# ATTiny85_5LED_R1.net
KiCad netlist of a schematic drawn in EAGLE
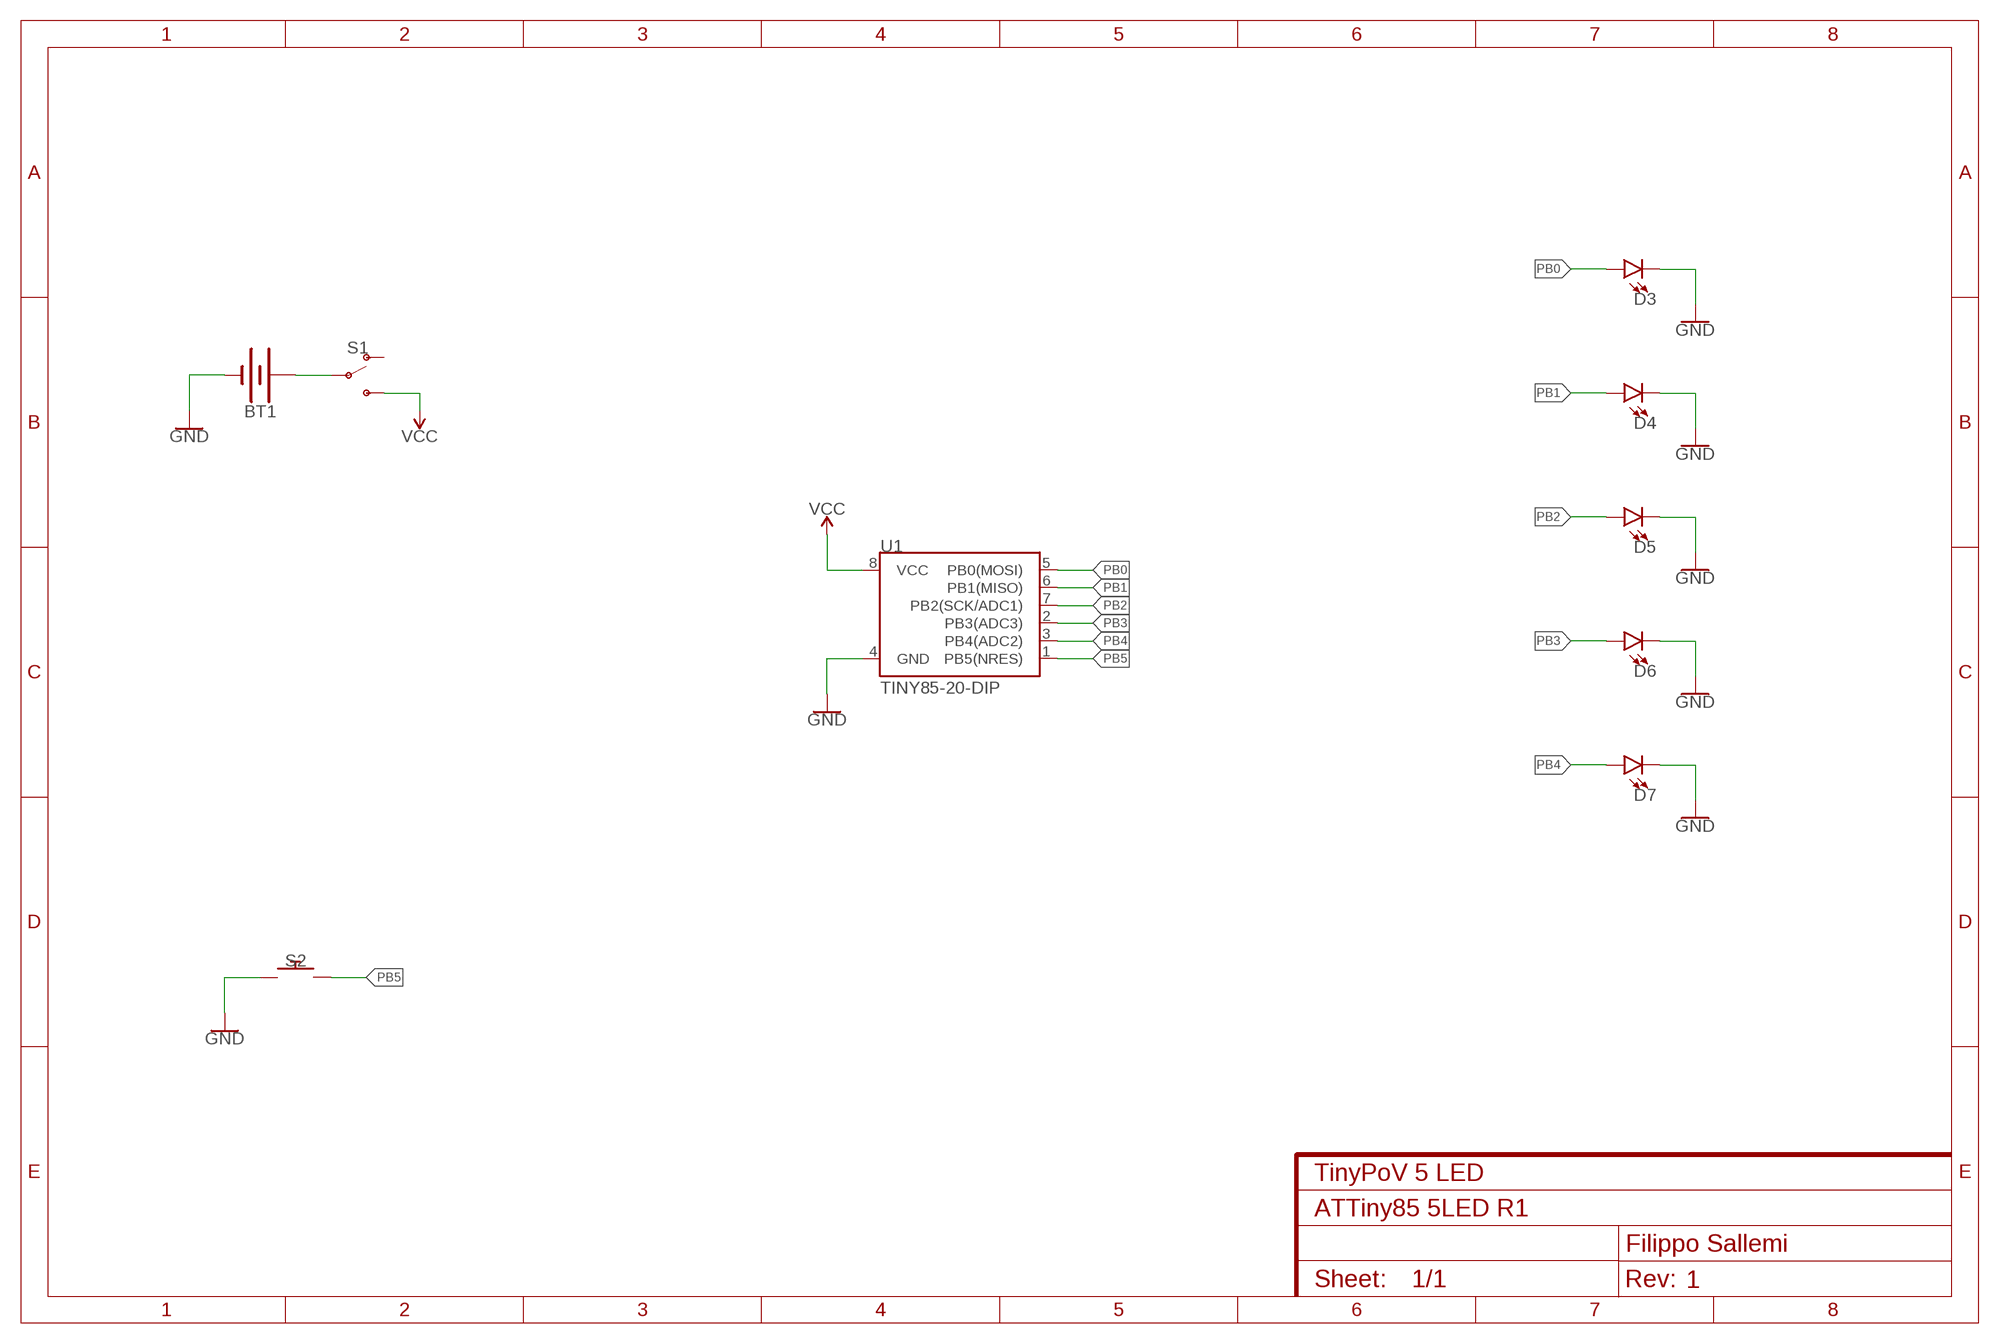
[diagram p0: schematic, sheet 1]

(export (version "E")
  (design (tool "Eeschema 10.0.6"))
  (components
    (comp (ref "BT1")
      (value "BATTERY-20MM_PTH")
      (footprint "eagle-import:BATTCOM_20MM_PTH")
      (libsource (lib "eagle-import") (part "BATTERY-20MM_PTH"))
    )
    (comp (ref "D3")
      (value "LED5MM")
      (footprint "eagle-import:LED_5MM")
      (libsource (lib "eagle-import") (part "LED5MM"))
    )
    (comp (ref "D4")
      (value "LED5MM")
      (footprint "eagle-import:LED_5MM")
      (libsource (lib "eagle-import") (part "LED5MM"))
    )
    (comp (ref "D5")
      (value "LED5MM")
      (footprint "eagle-import:LED_5MM")
      (libsource (lib "eagle-import") (part "LED5MM"))
    )
    (comp (ref "D6")
      (value "LED5MM")
      (footprint "eagle-import:LED_5MM")
      (libsource (lib "eagle-import") (part "LED5MM"))
    )
    (comp (ref "D7")
      (value "LED5MM")
      (footprint "eagle-import:LED_5MM")
      (libsource (lib "eagle-import") (part "LED5MM"))
    )
    (comp (ref "S1")
      (value "SWITCH-SPDT-PTH-11.6X4.0MM-KIT")
      (footprint "eagle-import:SWITCH_SPDT_PTH_11.6X4.0MM_KIT")
      (libsource (lib "eagle-import") (part "SWITCH-SPDT-PTH-11.6X4.0MM-KIT"))
    )
    (comp (ref "S2")
      (value "SWITCH_PUSHBUTTONEVQ-PE")
      (footprint "eagle-import:TACT_PANA-EVQ")
      (libsource (lib "eagle-import") (part "SWITCH_PUSHBUTTONEVQ-PE"))
    )
    (comp (ref "U1")
      (value "TINY85-20-DIP")
      (footprint "eagle-import:DIP08_MCU")
      (libsource (lib "eagle-import") (part "ATTINY45TINY85-20-DIP"))
    )
  )
  (nets
    (net (code "1") (name "GND") (class "Default")
      (node (ref "BT1") (pin "2") (pinfunction "-_2") (pintype "power_in"))
      (node (ref "D3") (pin "K") (pinfunction "C_K") (pintype "passive"))
      (node (ref "D4") (pin "K") (pinfunction "C_K") (pintype "passive"))
      (node (ref "D5") (pin "K") (pinfunction "C_K") (pintype "passive"))
      (node (ref "D6") (pin "K") (pinfunction "C_K") (pintype "passive"))
      (node (ref "D7") (pin "K") (pinfunction "C_K") (pintype "passive"))
      (node (ref "S2") (pin "P$1") (pinfunction "P$1_P$1") (pintype "passive"))
      (node (ref "U1") (pin "4") (pinfunction "GND_4") (pintype "bidirectional"))
    )
    (net (code "2") (name "Net-(BT1-+)") (class "Default")
      (node (ref "BT1") (pin "1") (pinfunction "+_1") (pintype "power_in"))
      (node (ref "S1") (pin "2") (pinfunction "P_2") (pintype "passive"))
    )
    (net (code "3") (name "PB0") (class "Default")
      (node (ref "D3") (pin "A") (pinfunction "A_A") (pintype "passive"))
      (node (ref "U1") (pin "5") (pinfunction "PB0(MOSI)_5") (pintype "bidirectional"))
    )
    (net (code "4") (name "PB1") (class "Default")
      (node (ref "D4") (pin "A") (pinfunction "A_A") (pintype "passive"))
      (node (ref "U1") (pin "6") (pinfunction "PB1(MISO)_6") (pintype "bidirectional"))
    )
    (net (code "5") (name "PB2") (class "Default")
      (node (ref "D5") (pin "A") (pinfunction "A_A") (pintype "passive"))
      (node (ref "U1") (pin "7") (pinfunction "PB2(SCK/ADC1)_7") (pintype "bidirectional"))
    )
    (net (code "6") (name "PB3") (class "Default")
      (node (ref "D6") (pin "A") (pinfunction "A_A") (pintype "passive"))
      (node (ref "U1") (pin "2") (pinfunction "PB3(ADC3)_2") (pintype "bidirectional"))
    )
    (net (code "7") (name "PB4") (class "Default")
      (node (ref "D7") (pin "A") (pinfunction "A_A") (pintype "passive"))
      (node (ref "U1") (pin "3") (pinfunction "PB4(ADC2)_3") (pintype "bidirectional"))
    )
    (net (code "8") (name "PB5") (class "Default")
      (node (ref "S2") (pin "P$2") (pinfunction "P$2_P$2") (pintype "passive"))
      (node (ref "U1") (pin "1") (pinfunction "PB5(NRES)_1") (pintype "bidirectional"))
    )
    (net (code "9") (name "VCC") (class "Default")
      (node (ref "S1") (pin "3") (pinfunction "S_3") (pintype "passive"))
      (node (ref "U1") (pin "8") (pinfunction "VCC_8") (pintype "bidirectional"))
    )
    (net (code "10") (name "unconnected-(S1-O-Pad1)") (class "Default")
      (node (ref "S1") (pin "1") (pinfunction "O_1") (pintype "passive"))
    )
  )
)
